# button.net
KiCad netlist of a schematic drawn in EAGLE
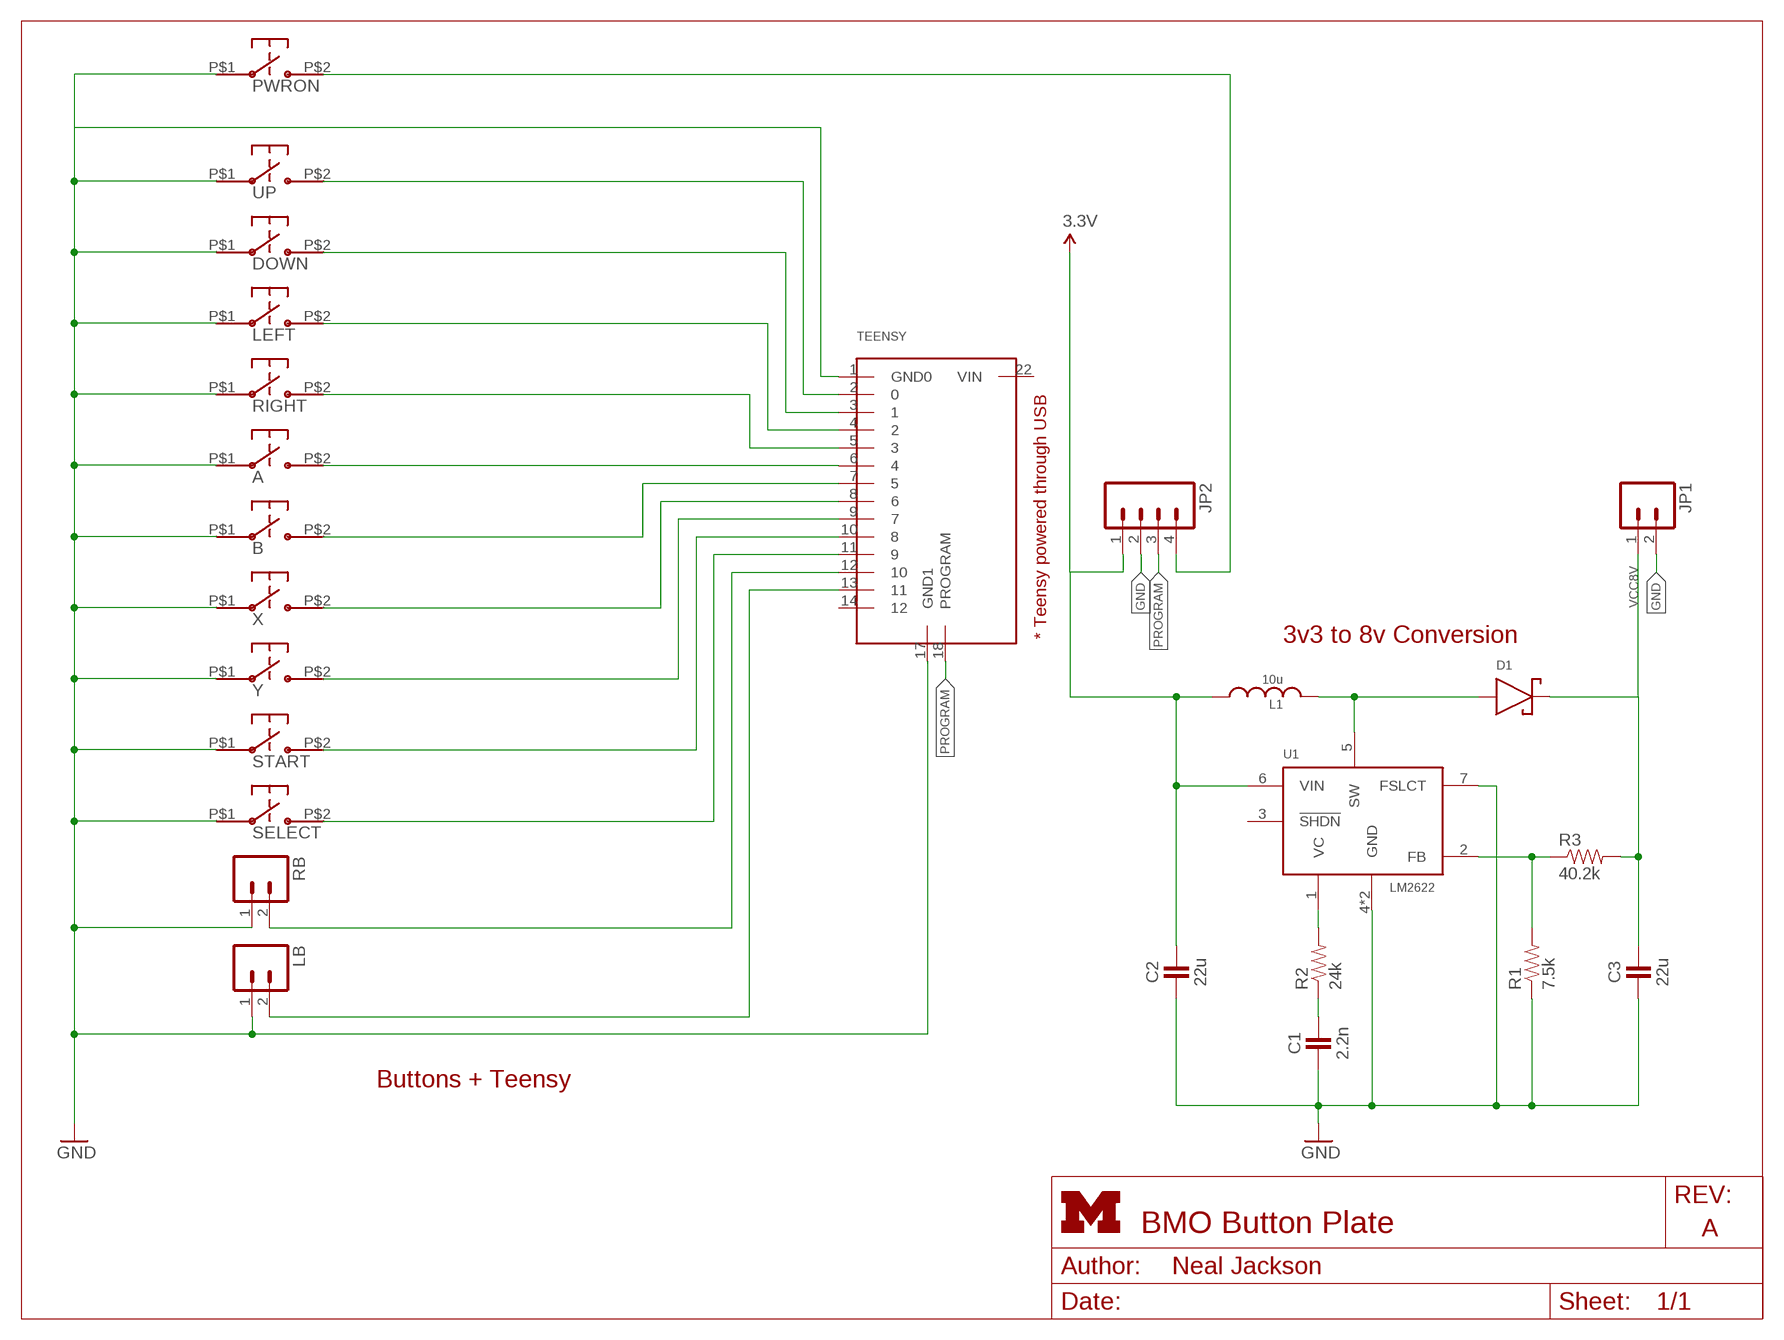
[diagram p0: schematic, sheet 1]

(export (version "E")
  (design (tool "Eeschema 10.0.6"))
  (components
    (comp (ref "A")
      (value "SKPDAMD010")
      (footprint "eagle-import:SKPDAMD010")
      (libsource (lib "eagle-import") (part "SKPDAMD010"))
    )
    (comp (ref "B")
      (value "SKPDAMD010")
      (footprint "eagle-import:SKPDAMD010")
      (libsource (lib "eagle-import") (part "SKPDAMD010"))
    )
    (comp (ref "C1")
      (value "2.2n")
      (footprint "eagle-import:0402_CAP")
      (libsource (lib "eagle-import") (part "CAPACITOR"))
    )
    (comp (ref "C2")
      (value "22u")
      (footprint "eagle-import:0402_CAP")
      (libsource (lib "eagle-import") (part "CAPACITOR"))
    )
    (comp (ref "C3")
      (value "22u")
      (footprint "eagle-import:0402_CAP")
      (libsource (lib "eagle-import") (part "CAPACITOR"))
    )
    (comp (ref "D1")
      (value "MBRM140T3G")
      (footprint "eagle-import:DO-216AA")
      (libsource (lib "eagle-import") (part "MBRM140T3G"))
    )
    (comp (ref "DOWN")
      (value "SKPDAMD010")
      (footprint "eagle-import:SKPDAMD010")
      (libsource (lib "eagle-import") (part "SKPDAMD010"))
    )
    (comp (ref "JP1")
      (value "M02PTH")
      (footprint "eagle-import:1X02")
      (libsource (lib "eagle-import") (part "M02PTH"))
    )
    (comp (ref "JP2")
      (value "M04PTH")
      (footprint "eagle-import:1X04")
      (libsource (lib "eagle-import") (part "M04PTH"))
    )
    (comp (ref "L1")
      (value "10u")
      (footprint "eagle-import:0402_CAP")
      (libsource (lib "eagle-import") (part "INDUCTOR0402"))
    )
    (comp (ref "LB")
      (value "M02PTH")
      (footprint "eagle-import:1X02")
      (libsource (lib "eagle-import") (part "M02PTH"))
    )
    (comp (ref "LEFT")
      (value "SKPDAMD010")
      (footprint "eagle-import:SKPDAMD010")
      (libsource (lib "eagle-import") (part "SKPDAMD010"))
    )
    (comp (ref "PWRON")
      (value "SKPDAMD010")
      (footprint "eagle-import:SKPDAMD010")
      (libsource (lib "eagle-import") (part "SKPDAMD010"))
    )
    (comp (ref "R1")
      (value "7.5k")
      (footprint "eagle-import:0402_RES")
      (libsource (lib "eagle-import") (part "RESISTOR0402_RES"))
    )
    (comp (ref "R2")
      (value "24k")
      (footprint "eagle-import:0402_RES")
      (libsource (lib "eagle-import") (part "RESISTOR0402_RES"))
    )
    (comp (ref "R3")
      (value "40.2k")
      (footprint "eagle-import:0402_RES")
      (libsource (lib "eagle-import") (part "RESISTOR0402_RES"))
    )
    (comp (ref "RB")
      (value "M02PTH")
      (footprint "eagle-import:1X02")
      (libsource (lib "eagle-import") (part "M02PTH"))
    )
    (comp (ref "RIGHT")
      (value "SKPDAMD010")
      (footprint "eagle-import:SKPDAMD010")
      (libsource (lib "eagle-import") (part "SKPDAMD010"))
    )
    (comp (ref "SELECT")
      (value "EVQ11D09K")
      (footprint "eagle-import:EVQ11D09K")
      (libsource (lib "eagle-import") (part "EVQ11D09K"))
    )
    (comp (ref "START")
      (value "EVQ11D09K")
      (footprint "eagle-import:EVQ11D09K")
      (libsource (lib "eagle-import") (part "EVQ11D09K"))
    )
    (comp (ref "TEENSY")
      (value "TEENSY_LC")
      (footprint "eagle-import:TEENSY_LC")
      (libsource (lib "eagle-import") (part "TEENSY_LC"))
    )
    (comp (ref "U1")
      (value "LM2622")
      (footprint "eagle-import:MSOP8")
      (libsource (lib "eagle-import") (part "LM2622"))
    )
    (comp (ref "UP")
      (value "SKPDAMD010")
      (footprint "eagle-import:SKPDAMD010")
      (libsource (lib "eagle-import") (part "SKPDAMD010"))
    )
    (comp (ref "X")
      (value "SKPDAMD010")
      (footprint "eagle-import:SKPDAMD010")
      (libsource (lib "eagle-import") (part "SKPDAMD010"))
    )
    (comp (ref "Y")
      (value "SKPDAMD010")
      (footprint "eagle-import:SKPDAMD010")
      (libsource (lib "eagle-import") (part "SKPDAMD010"))
    )
  )
  (nets
    (net (code "1") (name "/VCC8V") (class "Default")
      (node (ref "C3") (pin "1") (pinfunction "1_1") (pintype "bidirectional"))
      (node (ref "D1") (pin "CATHODE") (pinfunction "CATHODE_CATHODE") (pintype "bidirectional"))
      (node (ref "JP1") (pin "1") (pinfunction "1_1") (pintype "passive"))
      (node (ref "R3") (pin "2") (pinfunction "2_2") (pintype "passive"))
    )
    (net (code "2") (name "3.3V") (class "Default")
      (node (ref "C2") (pin "1") (pinfunction "1_1") (pintype "bidirectional"))
      (node (ref "JP2") (pin "1") (pinfunction "1_1") (pintype "passive"))
      (node (ref "L1") (pin "1") (pinfunction "1_1") (pintype "bidirectional"))
      (node (ref "U1") (pin "6") (pinfunction "VIN_6") (pintype "bidirectional"))
    )
    (net (code "3") (name "GND") (class "Default")
      (node (ref "A") (pin "P$1") (pinfunction "P$1_P$1") (pintype "passive"))
      (node (ref "B") (pin "P$1") (pinfunction "P$1_P$1") (pintype "passive"))
      (node (ref "C1") (pin "2") (pinfunction "2_2") (pintype "bidirectional"))
      (node (ref "C2") (pin "2") (pinfunction "2_2") (pintype "bidirectional"))
      (node (ref "C3") (pin "2") (pinfunction "2_2") (pintype "bidirectional"))
      (node (ref "DOWN") (pin "P$1") (pinfunction "P$1_P$1") (pintype "passive"))
      (node (ref "JP1") (pin "2") (pinfunction "2_2") (pintype "passive"))
      (node (ref "JP2") (pin "2") (pinfunction "2_2") (pintype "passive"))
      (node (ref "LB") (pin "1") (pinfunction "1_1") (pintype "passive"))
      (node (ref "LEFT") (pin "P$1") (pinfunction "P$1_P$1") (pintype "passive"))
      (node (ref "PWRON") (pin "P$1") (pinfunction "P$1_P$1") (pintype "passive"))
      (node (ref "R1") (pin "1") (pinfunction "1_1") (pintype "passive"))
      (node (ref "RB") (pin "1") (pinfunction "1_1") (pintype "passive"))
      (node (ref "RIGHT") (pin "P$1") (pinfunction "P$1_P$1") (pintype "passive"))
      (node (ref "SELECT") (pin "P$1") (pinfunction "P$1_P$1") (pintype "passive"))
      (node (ref "START") (pin "P$1") (pinfunction "P$1_P$1") (pintype "passive"))
      (node (ref "TEENSY") (pin "1") (pinfunction "GND0_1") (pintype "bidirectional"))
      (node (ref "TEENSY") (pin "17") (pinfunction "GND1_17") (pintype "bidirectional"))
      (node (ref "U1") (pin "4") (pinfunction "GND_4") (pintype "bidirectional"))
      (node (ref "U1") (pin "7") (pinfunction "FSLCT_7") (pintype "bidirectional"))
      (node (ref "U1") (pin "GND") (pinfunction "GND_GND") (pintype "bidirectional"))
      (node (ref "UP") (pin "P$1") (pinfunction "P$1_P$1") (pintype "passive"))
      (node (ref "X") (pin "P$1") (pinfunction "P$1_P$1") (pintype "passive"))
      (node (ref "Y") (pin "P$1") (pinfunction "P$1_P$1") (pintype "passive"))
    )
    (net (code "4") (name "Net-(C1-Pad1)") (class "Default")
      (node (ref "C1") (pin "1") (pinfunction "1_1") (pintype "bidirectional"))
      (node (ref "R2") (pin "1") (pinfunction "1_1") (pintype "passive"))
    )
    (net (code "5") (name "Net-(JP2-Pad4)") (class "Default")
      (node (ref "JP2") (pin "4") (pinfunction "4_4") (pintype "passive"))
      (node (ref "PWRON") (pin "P$2") (pinfunction "P$2_P$2") (pintype "passive"))
    )
    (net (code "6") (name "Net-(TEENSY-0)") (class "Default")
      (node (ref "TEENSY") (pin "2") (pinfunction "0_2") (pintype "bidirectional"))
      (node (ref "UP") (pin "P$2") (pinfunction "P$2_P$2") (pintype "passive"))
    )
    (net (code "7") (name "Net-(TEENSY-1)") (class "Default")
      (node (ref "DOWN") (pin "P$2") (pinfunction "P$2_P$2") (pintype "passive"))
      (node (ref "TEENSY") (pin "3") (pinfunction "1_3") (pintype "bidirectional"))
    )
    (net (code "8") (name "Net-(TEENSY-2)") (class "Default")
      (node (ref "LEFT") (pin "P$2") (pinfunction "P$2_P$2") (pintype "passive"))
      (node (ref "TEENSY") (pin "4") (pinfunction "2_4") (pintype "bidirectional"))
    )
    (net (code "9") (name "Net-(TEENSY-3)") (class "Default")
      (node (ref "RIGHT") (pin "P$2") (pinfunction "P$2_P$2") (pintype "passive"))
      (node (ref "TEENSY") (pin "5") (pinfunction "3_5") (pintype "bidirectional"))
    )
    (net (code "10") (name "Net-(TEENSY-4)") (class "Default")
      (node (ref "A") (pin "P$2") (pinfunction "P$2_P$2") (pintype "passive"))
      (node (ref "TEENSY") (pin "6") (pinfunction "4_6") (pintype "bidirectional"))
    )
    (net (code "11") (name "Net-(TEENSY-5)") (class "Default")
      (node (ref "B") (pin "P$2") (pinfunction "P$2_P$2") (pintype "passive"))
      (node (ref "TEENSY") (pin "7") (pinfunction "5_7") (pintype "bidirectional"))
    )
    (net (code "12") (name "Net-(TEENSY-6)") (class "Default")
      (node (ref "TEENSY") (pin "8") (pinfunction "6_8") (pintype "bidirectional"))
      (node (ref "X") (pin "P$2") (pinfunction "P$2_P$2") (pintype "passive"))
    )
    (net (code "13") (name "Net-(TEENSY-7)") (class "Default")
      (node (ref "TEENSY") (pin "9") (pinfunction "7_9") (pintype "bidirectional"))
      (node (ref "Y") (pin "P$2") (pinfunction "P$2_P$2") (pintype "passive"))
    )
    (net (code "14") (name "Net-(TEENSY-8)") (class "Default")
      (node (ref "START") (pin "P$2") (pinfunction "P$2_P$2") (pintype "passive"))
      (node (ref "TEENSY") (pin "10") (pinfunction "8_10") (pintype "bidirectional"))
    )
    (net (code "15") (name "Net-(TEENSY-9)") (class "Default")
      (node (ref "SELECT") (pin "P$2") (pinfunction "P$2_P$2") (pintype "passive"))
      (node (ref "TEENSY") (pin "11") (pinfunction "9_11") (pintype "bidirectional"))
    )
    (net (code "16") (name "Net-(TEENSY-10)") (class "Default")
      (node (ref "RB") (pin "2") (pinfunction "2_2") (pintype "passive"))
      (node (ref "TEENSY") (pin "12") (pinfunction "10_12") (pintype "bidirectional"))
    )
    (net (code "17") (name "Net-(TEENSY-11)") (class "Default")
      (node (ref "LB") (pin "2") (pinfunction "2_2") (pintype "passive"))
      (node (ref "TEENSY") (pin "13") (pinfunction "11_13") (pintype "bidirectional"))
    )
    (net (code "18") (name "Net-(U1-FB)") (class "Default")
      (node (ref "R1") (pin "2") (pinfunction "2_2") (pintype "passive"))
      (node (ref "R3") (pin "1") (pinfunction "1_1") (pintype "passive"))
      (node (ref "U1") (pin "2") (pinfunction "FB_2") (pintype "bidirectional"))
    )
    (net (code "19") (name "Net-(U1-SW)") (class "Default")
      (node (ref "D1") (pin "ANODE") (pinfunction "ANODE_ANODE") (pintype "bidirectional"))
      (node (ref "L1") (pin "2") (pinfunction "2_2") (pintype "bidirectional"))
      (node (ref "U1") (pin "5") (pinfunction "SW_5") (pintype "bidirectional"))
    )
    (net (code "20") (name "Net-(U1-VC)") (class "Default")
      (node (ref "R2") (pin "2") (pinfunction "2_2") (pintype "passive"))
      (node (ref "U1") (pin "1") (pinfunction "VC_1") (pintype "bidirectional"))
    )
    (net (code "21") (name "PROGRAM") (class "Default")
      (node (ref "JP2") (pin "3") (pinfunction "3_3") (pintype "passive"))
      (node (ref "TEENSY") (pin "18") (pinfunction "PROGRAM_18") (pintype "bidirectional"))
    )
    (net (code "22") (name "unconnected-(TEENSY-12-Pad14)") (class "Default")
      (node (ref "TEENSY") (pin "14") (pinfunction "12_14") (pintype "bidirectional"))
    )
    (net (code "23") (name "unconnected-(TEENSY-VIN-Pad22)") (class "Default")
      (node (ref "TEENSY") (pin "22") (pinfunction "VIN_22") (pintype "bidirectional"))
    )
    (net (code "24") (name "unconnected-(U1-~{SHDN}-Pad3)") (class "Default")
      (node (ref "U1") (pin "3") (pinfunction "~{SHDN}_3") (pintype "bidirectional"))
    )
  )
)
